# AV_Design.net
KiCad netlist of a schematic drawn in EAGLE
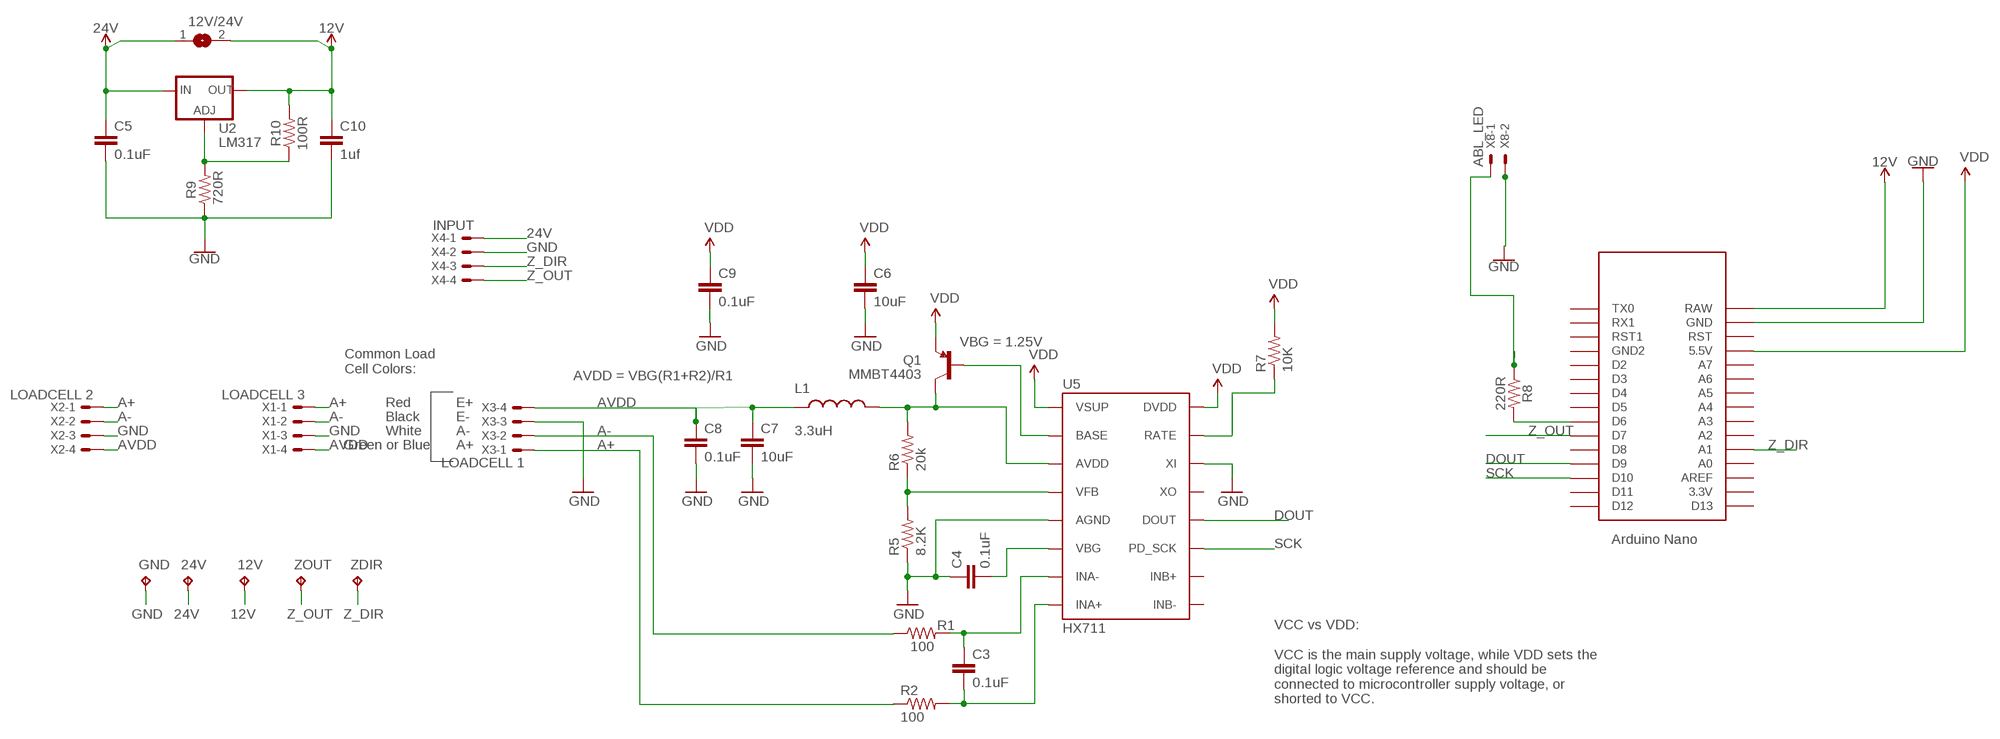
[diagram p0: schematic, sheet 1]

(export (version "E")
  (design (tool "Eeschema 10.0.6"))
  (components
    (comp (ref "12V")
      (value "TPB2,54")
      (footprint "eagle-import:B2,54")
      (libsource (lib "eagle-import") (part "TPB2,54"))
    )
    (comp (ref "12V/24V")
      (value "SJ")
      (footprint "eagle-import:SJ")
      (libsource (lib "eagle-import") (part "SJ"))
    )
    (comp (ref "24V")
      (value "TPB2,54")
      (footprint "eagle-import:B2,54")
      (libsource (lib "eagle-import") (part "TPB2,54"))
    )
    (comp (ref "C3")
      (value "0.1uF")
      (footprint "eagle-import:0603-CAP")
      (libsource (lib "eagle-import") (part "0.1UF-25V-5%(0603)"))
    )
    (comp (ref "C4")
      (value "0.1uF")
      (footprint "eagle-import:0603-CAP")
      (libsource (lib "eagle-import") (part "0.1UF-25V-5%(0603)"))
    )
    (comp (ref "C5")
      (value "0.1uF")
      (footprint "eagle-import:0603")
      (libsource (lib "eagle-import") (part "9.0PF-0603-50V-10%"))
    )
    (comp (ref "C6")
      (value "10uF")
      (footprint "eagle-import:1210")
      (libsource (lib "eagle-import") (part "10UF50V20%(1210)"))
    )
    (comp (ref "C7")
      (value "10uF")
      (footprint "eagle-import:1210")
      (libsource (lib "eagle-import") (part "10UF50V20%(1210)"))
    )
    (comp (ref "C8")
      (value "0.1uF")
      (footprint "eagle-import:0603-CAP")
      (libsource (lib "eagle-import") (part "0.1UF-25V-5%(0603)"))
    )
    (comp (ref "C9")
      (value "0.1uF")
      (footprint "eagle-import:0603-CAP")
      (libsource (lib "eagle-import") (part "0.1UF-25V-5%(0603)"))
    )
    (comp (ref "C10")
      (value "1uf")
      (footprint "eagle-import:0603")
      (libsource (lib "eagle-import") (part "9.0PF-0603-50V-10%"))
    )
    (comp (ref "GND")
      (value "TPB2,54")
      (footprint "eagle-import:B2,54")
      (libsource (lib "eagle-import") (part "TPB2,54"))
    )
    (comp (ref "L1")
      (value "3.3uH")
      (footprint "eagle-import:0805")
      (libsource (lib "eagle-import") (part "INDUCTOR0805-IND"))
    )
    (comp (ref "Q1")
      (value "MMBT4403")
      (footprint "eagle-import:SOT23-3")
      (libsource (lib "eagle-import") (part "TRANSISTOR_PNPMMBT4403"))
    )
    (comp (ref "R1")
      (value "100")
      (footprint "eagle-import:0603-RES")
      (libsource (lib "eagle-import") (part "100OHM-1/10W-1%(0603)"))
    )
    (comp (ref "R2")
      (value "100")
      (footprint "eagle-import:0603-RES")
      (libsource (lib "eagle-import") (part "100OHM-1/10W-1%(0603)"))
    )
    (comp (ref "R5")
      (value "8.2K")
      (footprint "eagle-import:0603-RES")
      (libsource (lib "eagle-import") (part "8.2KOHM-1/10W-5%(0603)"))
    )
    (comp (ref "R6")
      (value "20k")
      (footprint "eagle-import:0603-RES")
      (libsource (lib "eagle-import") (part "20KOHM1/10W1%(0603)"))
    )
    (comp (ref "R7")
      (value "10K")
      (footprint "eagle-import:0603-RES")
      (libsource (lib "eagle-import") (part "10KOHM-1/10W-1%(0603)0603"))
    )
    (comp (ref "R8")
      (value "220R")
      (footprint "eagle-import:0603")
      (libsource (lib "eagle-import") (part "RESISTOR0603"))
    )
    (comp (ref "R9")
      (value "720R")
      (footprint "eagle-import:0603")
      (libsource (lib "eagle-import") (part "RESISTOR0603"))
    )
    (comp (ref "R10")
      (value "100R")
      (footprint "eagle-import:0603")
      (libsource (lib "eagle-import") (part "RESISTOR0603"))
    )
    (comp (ref "U$1")
      (value "NANO")
      (footprint "eagle-import:NANO")
      (libsource (lib "eagle-import") (part "NANO"))
    )
    (comp (ref "U2")
      (value "LM317")
      (footprint "eagle-import:SOT223")
      (libsource (lib "eagle-import") (part "V_REG_317SMD"))
    )
    (comp (ref "U5")
      (value "HX711")
      (footprint "eagle-import:SO16")
      (libsource (lib "eagle-import") (part "HX711HX711"))
    )
    (comp (ref "X1")
      (value "LOADCELL 3")
      (footprint "eagle-import:JST-XH-04-PACKAGE-LONG-PAD")
      (libsource (lib "eagle-import") (part "JST-XH-04-PIN-LONG-PAD"))
    )
    (comp (ref "X2")
      (value "LOADCELL 2")
      (footprint "eagle-import:JST-XH-04-PACKAGE-LONG-PAD")
      (libsource (lib "eagle-import") (part "JST-XH-04-PIN-LONG-PAD"))
    )
    (comp (ref "X3")
      (value "LOADCELL 1")
      (footprint "eagle-import:JST-XH-04-PACKAGE-LONG-PAD")
      (libsource (lib "eagle-import") (part "JST-XH-04-PIN-LONG-PAD"))
    )
    (comp (ref "X4")
      (value "INPUT")
      (footprint "eagle-import:JST-XH-04-PACKAGE-LONG-PAD")
      (libsource (lib "eagle-import") (part "JST-XH-04-PIN-LONG-PAD"))
    )
    (comp (ref "X8")
      (value "ABL_LED")
      (footprint "eagle-import:JST-XH-02-PACKAGE-LONG-PAD")
      (libsource (lib "eagle-import") (part "JST-XH-02-PIN-LONG-PAD"))
    )
    (comp (ref "ZDIR")
      (value "TPB2,54")
      (footprint "eagle-import:B2,54")
      (libsource (lib "eagle-import") (part "TPB2,54"))
    )
    (comp (ref "ZOUT")
      (value "TPB2,54")
      (footprint "eagle-import:B2,54")
      (libsource (lib "eagle-import") (part "TPB2,54"))
    )
  )
  (nets
    (net (code "1") (name "/A+") (class "Default")
      (node (ref "R2") (pin "1") (pinfunction "1_1") (pintype "passive"))
      (node (ref "X1") (pin "1") (pinfunction "S_1") (pintype "passive"))
      (node (ref "X2") (pin "1") (pinfunction "S_1") (pintype "passive"))
      (node (ref "X3") (pin "1") (pinfunction "S_1") (pintype "passive"))
    )
    (net (code "2") (name "/A-") (class "Default")
      (node (ref "R1") (pin "1") (pinfunction "1_1") (pintype "passive"))
      (node (ref "X1") (pin "2") (pinfunction "S_2") (pintype "passive"))
      (node (ref "X2") (pin "2") (pinfunction "S_2") (pintype "passive"))
      (node (ref "X3") (pin "2") (pinfunction "S_2") (pintype "passive"))
    )
    (net (code "3") (name "/AVDD") (class "Default")
      (node (ref "C7") (pin "1") (pinfunction "1_1") (pintype "passive"))
      (node (ref "C8") (pin "1") (pinfunction "1_1") (pintype "passive"))
      (node (ref "L1") (pin "1") (pinfunction "1_1") (pintype "passive"))
      (node (ref "X1") (pin "4") (pinfunction "S_4") (pintype "passive"))
      (node (ref "X2") (pin "4") (pinfunction "S_4") (pintype "passive"))
      (node (ref "X3") (pin "4") (pinfunction "S_4") (pintype "passive"))
    )
    (net (code "4") (name "/DOUT") (class "Default")
      (node (ref "U$1") (pin "D9") (pinfunction "D9_D9") (pintype "bidirectional"))
      (node (ref "U5") (pin "12") (pinfunction "DOUT_12") (pintype "bidirectional"))
    )
    (net (code "5") (name "/SCK") (class "Default")
      (node (ref "U$1") (pin "D10") (pinfunction "D10_D10") (pintype "bidirectional"))
      (node (ref "U5") (pin "11") (pinfunction "PD_SCK_11") (pintype "bidirectional"))
    )
    (net (code "6") (name "/Z_DIR") (class "Default")
      (node (ref "U$1") (pin "A1") (pinfunction "A1_A1") (pintype "bidirectional"))
      (node (ref "X4") (pin "3") (pinfunction "S_3") (pintype "passive"))
      (node (ref "ZDIR") (pin "TP") (pinfunction "TP_TP") (pintype "input"))
    )
    (net (code "7") (name "/Z_OUT") (class "Default")
      (node (ref "U$1") (pin "D7") (pinfunction "D7_D7") (pintype "bidirectional"))
      (node (ref "X4") (pin "4") (pinfunction "S_4") (pintype "passive"))
      (node (ref "ZOUT") (pin "TP") (pinfunction "TP_TP") (pintype "input"))
    )
    (net (code "8") (name "12V") (class "Default")
      (node (ref "12V") (pin "TP") (pinfunction "TP_TP") (pintype "input"))
      (node (ref "12V/24V") (pin "2") (pinfunction "2_2") (pintype "passive"))
      (node (ref "C10") (pin "1") (pinfunction "1_1") (pintype "passive"))
      (node (ref "R10") (pin "2") (pinfunction "2_2") (pintype "passive"))
      (node (ref "U$1") (pin "RAW") (pinfunction "RAW_RAW") (pintype "bidirectional"))
      (node (ref "U2") (pin "2") (pinfunction "OUT_2") (pintype "output"))
    )
    (net (code "9") (name "24V") (class "Default")
      (node (ref "12V/24V") (pin "1") (pinfunction "1_1") (pintype "passive"))
      (node (ref "24V") (pin "TP") (pinfunction "TP_TP") (pintype "input"))
      (node (ref "C5") (pin "1") (pinfunction "1_1") (pintype "passive"))
      (node (ref "U2") (pin "3") (pinfunction "IN_3") (pintype "input"))
      (node (ref "X4") (pin "1") (pinfunction "S_1") (pintype "passive"))
    )
    (net (code "10") (name "GND") (class "Default")
      (node (ref "C10") (pin "2") (pinfunction "2_2") (pintype "passive"))
      (node (ref "C4") (pin "1") (pinfunction "1_1") (pintype "passive"))
      (node (ref "C5") (pin "2") (pinfunction "2_2") (pintype "passive"))
      (node (ref "C6") (pin "2") (pinfunction "2_2") (pintype "passive"))
      (node (ref "C7") (pin "2") (pinfunction "2_2") (pintype "passive"))
      (node (ref "C8") (pin "2") (pinfunction "2_2") (pintype "passive"))
      (node (ref "C9") (pin "2") (pinfunction "2_2") (pintype "passive"))
      (node (ref "GND") (pin "TP") (pinfunction "TP_TP") (pintype "input"))
      (node (ref "R5") (pin "1") (pinfunction "1_1") (pintype "passive"))
      (node (ref "R9") (pin "1") (pinfunction "1_1") (pintype "passive"))
      (node (ref "U$1") (pin "GND") (pinfunction "GND_GND") (pintype "bidirectional"))
      (node (ref "U5") (pin "14") (pinfunction "XI_14") (pintype "bidirectional"))
      (node (ref "U5") (pin "5") (pinfunction "AGND_5") (pintype "bidirectional"))
      (node (ref "X1") (pin "3") (pinfunction "S_3") (pintype "passive"))
      (node (ref "X2") (pin "3") (pinfunction "S_3") (pintype "passive"))
      (node (ref "X3") (pin "3") (pinfunction "S_3") (pintype "passive"))
      (node (ref "X4") (pin "2") (pinfunction "S_2") (pintype "passive"))
      (node (ref "X8") (pin "2") (pinfunction "S_2") (pintype "passive"))
    )
    (net (code "11") (name "Net-(Q1-B)") (class "Default")
      (node (ref "Q1") (pin "1") (pinfunction "B_1") (pintype "passive"))
      (node (ref "U5") (pin "2") (pinfunction "BASE_2") (pintype "bidirectional"))
    )
    (net (code "12") (name "Net-(Q1-C)") (class "Default")
      (node (ref "L1") (pin "2") (pinfunction "2_2") (pintype "passive"))
      (node (ref "Q1") (pin "3") (pinfunction "C_3") (pintype "passive"))
      (node (ref "R6") (pin "2") (pinfunction "2_2") (pintype "passive"))
      (node (ref "U5") (pin "3") (pinfunction "AVDD_3") (pintype "bidirectional"))
    )
    (net (code "13") (name "Net-(R8-Pad2)") (class "Default")
      (node (ref "R8") (pin "2") (pinfunction "2_2") (pintype "passive"))
      (node (ref "U$1") (pin "D6") (pinfunction "D6_D6") (pintype "bidirectional"))
    )
    (net (code "14") (name "Net-(U2-ADJ)") (class "Default")
      (node (ref "R10") (pin "1") (pinfunction "1_1") (pintype "passive"))
      (node (ref "R9") (pin "2") (pinfunction "2_2") (pintype "passive"))
      (node (ref "U2") (pin "1") (pinfunction "ADJ_1") (pintype "input"))
    )
    (net (code "15") (name "Net-(U5-INA+)") (class "Default")
      (node (ref "C3") (pin "2") (pinfunction "2_2") (pintype "passive"))
      (node (ref "R2") (pin "2") (pinfunction "2_2") (pintype "passive"))
      (node (ref "U5") (pin "8") (pinfunction "INA+_8") (pintype "bidirectional"))
    )
    (net (code "16") (name "Net-(U5-INA-)") (class "Default")
      (node (ref "C3") (pin "1") (pinfunction "1_1") (pintype "passive"))
      (node (ref "R1") (pin "2") (pinfunction "2_2") (pintype "passive"))
      (node (ref "U5") (pin "7") (pinfunction "INA-_7") (pintype "bidirectional"))
    )
    (net (code "17") (name "Net-(U5-RATE)") (class "Default")
      (node (ref "R7") (pin "1") (pinfunction "1_1") (pintype "passive"))
      (node (ref "U5") (pin "15") (pinfunction "RATE_15") (pintype "bidirectional"))
    )
    (net (code "18") (name "Net-(U5-VBG)") (class "Default")
      (node (ref "C4") (pin "2") (pinfunction "2_2") (pintype "passive"))
      (node (ref "U5") (pin "6") (pinfunction "VBG_6") (pintype "bidirectional"))
    )
    (net (code "19") (name "Net-(U5-VFB)") (class "Default")
      (node (ref "R5") (pin "2") (pinfunction "2_2") (pintype "passive"))
      (node (ref "R6") (pin "1") (pinfunction "1_1") (pintype "passive"))
      (node (ref "U5") (pin "4") (pinfunction "VFB_4") (pintype "bidirectional"))
    )
    (net (code "20") (name "Net-(X8A-S)") (class "Default")
      (node (ref "R8") (pin "1") (pinfunction "1_1") (pintype "passive"))
      (node (ref "X8") (pin "1") (pinfunction "S_1") (pintype "passive"))
    )
    (net (code "21") (name "VDD") (class "Default")
      (node (ref "C6") (pin "1") (pinfunction "1_1") (pintype "passive"))
      (node (ref "C9") (pin "1") (pinfunction "1_1") (pintype "passive"))
      (node (ref "Q1") (pin "2") (pinfunction "E_2") (pintype "passive"))
      (node (ref "R7") (pin "2") (pinfunction "2_2") (pintype "passive"))
      (node (ref "U$1") (pin "5V") (pinfunction "5.5V_5V") (pintype "bidirectional"))
      (node (ref "U5") (pin "1") (pinfunction "VSUP_1") (pintype "bidirectional"))
      (node (ref "U5") (pin "16") (pinfunction "DVDD_16") (pintype "bidirectional"))
    )
    (net (code "22") (name "unconnected-(U$1-GND2-PadGND1)") (class "Default")
      (node (ref "U$1") (pin "GND1") (pinfunction "GND2_GND1") (pintype "bidirectional"))
    )
    (net (code "23") (name "unconnected-(U$1-Pad3.3V)") (class "Default")
      (node (ref "U$1") (pin "3.3V") (pinfunction "3.3V_3.3V") (pintype "bidirectional"))
    )
    (net (code "24") (name "unconnected-(U$1-PadA0)") (class "Default")
      (node (ref "U$1") (pin "A0") (pinfunction "A0_A0") (pintype "bidirectional"))
    )
    (net (code "25") (name "unconnected-(U$1-PadA2)") (class "Default")
      (node (ref "U$1") (pin "A2") (pinfunction "A2_A2") (pintype "bidirectional"))
    )
    (net (code "26") (name "unconnected-(U$1-PadA3)") (class "Default")
      (node (ref "U$1") (pin "A3") (pinfunction "A3_A3") (pintype "bidirectional"))
    )
    (net (code "27") (name "unconnected-(U$1-PadA4)") (class "Default")
      (node (ref "U$1") (pin "A4") (pinfunction "A4_A4") (pintype "bidirectional"))
    )
    (net (code "28") (name "unconnected-(U$1-PadA5)") (class "Default")
      (node (ref "U$1") (pin "A5") (pinfunction "A5_A5") (pintype "bidirectional"))
    )
    (net (code "29") (name "unconnected-(U$1-PadA6)") (class "Default")
      (node (ref "U$1") (pin "A6") (pinfunction "A6_A6") (pintype "bidirectional"))
    )
    (net (code "30") (name "unconnected-(U$1-PadA7)") (class "Default")
      (node (ref "U$1") (pin "A7") (pinfunction "A7_A7") (pintype "bidirectional"))
    )
    (net (code "31") (name "unconnected-(U$1-PadAREF)") (class "Default")
      (node (ref "U$1") (pin "AREF") (pinfunction "AREF_AREF") (pintype "bidirectional"))
    )
    (net (code "32") (name "unconnected-(U$1-PadD2)") (class "Default")
      (node (ref "U$1") (pin "D2") (pinfunction "D2_D2") (pintype "bidirectional"))
    )
    (net (code "33") (name "unconnected-(U$1-PadD3)") (class "Default")
      (node (ref "U$1") (pin "D3") (pinfunction "D3_D3") (pintype "bidirectional"))
    )
    (net (code "34") (name "unconnected-(U$1-PadD4)") (class "Default")
      (node (ref "U$1") (pin "D4") (pinfunction "D4_D4") (pintype "bidirectional"))
    )
    (net (code "35") (name "unconnected-(U$1-PadD5)") (class "Default")
      (node (ref "U$1") (pin "D5") (pinfunction "D5_D5") (pintype "bidirectional"))
    )
    (net (code "36") (name "unconnected-(U$1-PadD8)") (class "Default")
      (node (ref "U$1") (pin "D8") (pinfunction "D8_D8") (pintype "bidirectional"))
    )
    (net (code "37") (name "unconnected-(U$1-PadD11)") (class "Default")
      (node (ref "U$1") (pin "D11") (pinfunction "D11_D11") (pintype "bidirectional"))
    )
    (net (code "38") (name "unconnected-(U$1-PadD12)") (class "Default")
      (node (ref "U$1") (pin "D12") (pinfunction "D12_D12") (pintype "bidirectional"))
    )
    (net (code "39") (name "unconnected-(U$1-PadD13)") (class "Default")
      (node (ref "U$1") (pin "D13") (pinfunction "D13_D13") (pintype "bidirectional"))
    )
    (net (code "40") (name "unconnected-(U$1-PadICSP1)") (class "Default")
      (node (ref "U$1") (pin "ICSP1") (pinfunction "ICSP1_ICSP1") (pintype "bidirectional"))
    )
    (net (code "41") (name "unconnected-(U$1-PadICSP2)") (class "Default")
      (node (ref "U$1") (pin "ICSP2") (pinfunction "ICSP2_ICSP2") (pintype "bidirectional"))
    )
    (net (code "42") (name "unconnected-(U$1-PadICSP3)") (class "Default")
      (node (ref "U$1") (pin "ICSP3") (pinfunction "ICSP3_ICSP3") (pintype "bidirectional"))
    )
    (net (code "43") (name "unconnected-(U$1-PadICSP4)") (class "Default")
      (node (ref "U$1") (pin "ICSP4") (pinfunction "ICSP4_ICSP4") (pintype "bidirectional"))
    )
    (net (code "44") (name "unconnected-(U$1-PadICSP5)") (class "Default")
      (node (ref "U$1") (pin "ICSP5") (pinfunction "ICSP5_ICSP5") (pintype "bidirectional"))
    )
    (net (code "45") (name "unconnected-(U$1-PadICSP6)") (class "Default")
      (node (ref "U$1") (pin "ICSP6") (pinfunction "ICSP6_ICSP6") (pintype "bidirectional"))
    )
    (net (code "46") (name "unconnected-(U$1-PadRST)") (class "Default")
      (node (ref "U$1") (pin "RST") (pinfunction "RST_RST") (pintype "bidirectional"))
    )
    (net (code "47") (name "unconnected-(U$1-PadRST1)") (class "Default")
      (node (ref "U$1") (pin "RST1") (pinfunction "RST1_RST1") (pintype "bidirectional"))
    )
    (net (code "48") (name "unconnected-(U$1-PadRX1)") (class "Default")
      (node (ref "U$1") (pin "RX1") (pinfunction "RX1_RX1") (pintype "bidirectional"))
    )
    (net (code "49") (name "unconnected-(U$1-PadTX0)") (class "Default")
      (node (ref "U$1") (pin "TX0") (pinfunction "TX0_TX0") (pintype "bidirectional"))
    )
    (net (code "50") (name "unconnected-(U5-INB+-Pad10)") (class "Default")
      (node (ref "U5") (pin "10") (pinfunction "INB+_10") (pintype "bidirectional"))
    )
    (net (code "51") (name "unconnected-(U5-INB--Pad9)") (class "Default")
      (node (ref "U5") (pin "9") (pinfunction "INB-_9") (pintype "bidirectional"))
    )
    (net (code "52") (name "unconnected-(U5-XO-Pad13)") (class "Default")
      (node (ref "U5") (pin "13") (pinfunction "XO_13") (pintype "bidirectional"))
    )
  )
)
